# mosfet_saturation.net
KiCad netlist of a schematic drawn in EAGLE
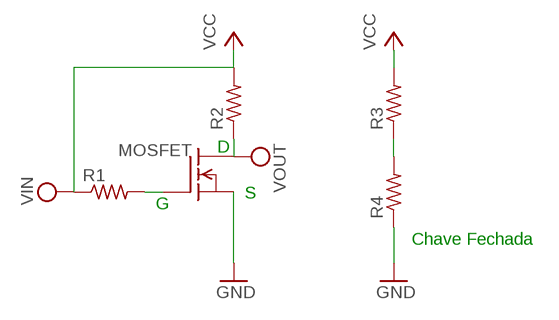
[diagram p0: schematic, sheet 1]

(export (version "E")
  (design (tool "Eeschema 10.0.6"))
  (components
    (comp (ref "MOSFET")
      (value "BSS97")
      (footprint "eagle-import:TO202")
      (libsource (lib "eagle-import") (part "BSS97"))
    )
    (comp (ref "R1")
      (value "R-US_0204/2V")
      (footprint "eagle-import:0204V")
      (libsource (lib "eagle-import") (part "R-US_0204/2V"))
    )
    (comp (ref "R2")
      (value "R-US_0204/2V")
      (footprint "eagle-import:0204V")
      (libsource (lib "eagle-import") (part "R-US_0204/2V"))
    )
    (comp (ref "R3")
      (value "R-US_0204/2V")
      (footprint "eagle-import:0204V")
      (libsource (lib "eagle-import") (part "R-US_0204/2V"))
    )
    (comp (ref "R4")
      (value "R-US_0204/2V")
      (footprint "eagle-import:0204V")
      (libsource (lib "eagle-import") (part "R-US_0204/2V"))
    )
  )
  (nets
    (net (code "1") (name "GND") (class "Default")
      (node (ref "MOSFET") (pin "1") (pinfunction "S_1") (pintype "passive"))
      (node (ref "R4") (pin "1") (pinfunction "1_1") (pintype "passive"))
    )
    (net (code "2") (name "Net-(MOSFET-D)") (class "Default")
      (node (ref "MOSFET") (pin "2") (pinfunction "D_2") (pintype "passive"))
      (node (ref "R2") (pin "1") (pinfunction "1_1") (pintype "passive"))
    )
    (net (code "3") (name "Net-(MOSFET-G)") (class "Default")
      (node (ref "MOSFET") (pin "3") (pinfunction "G_3") (pintype "passive"))
      (node (ref "R1") (pin "2") (pinfunction "2_2") (pintype "passive"))
    )
    (net (code "4") (name "Net-(R3-Pad1)") (class "Default")
      (node (ref "R3") (pin "1") (pinfunction "1_1") (pintype "passive"))
      (node (ref "R4") (pin "2") (pinfunction "2_2") (pintype "passive"))
    )
    (net (code "5") (name "VCC") (class "Default")
      (node (ref "R1") (pin "1") (pinfunction "1_1") (pintype "passive"))
      (node (ref "R2") (pin "2") (pinfunction "2_2") (pintype "passive"))
      (node (ref "R3") (pin "2") (pinfunction "2_2") (pintype "passive"))
    )
  )
)
